# Source_Selection.net
KiCad netlist of a schematic drawn in Altium Designer
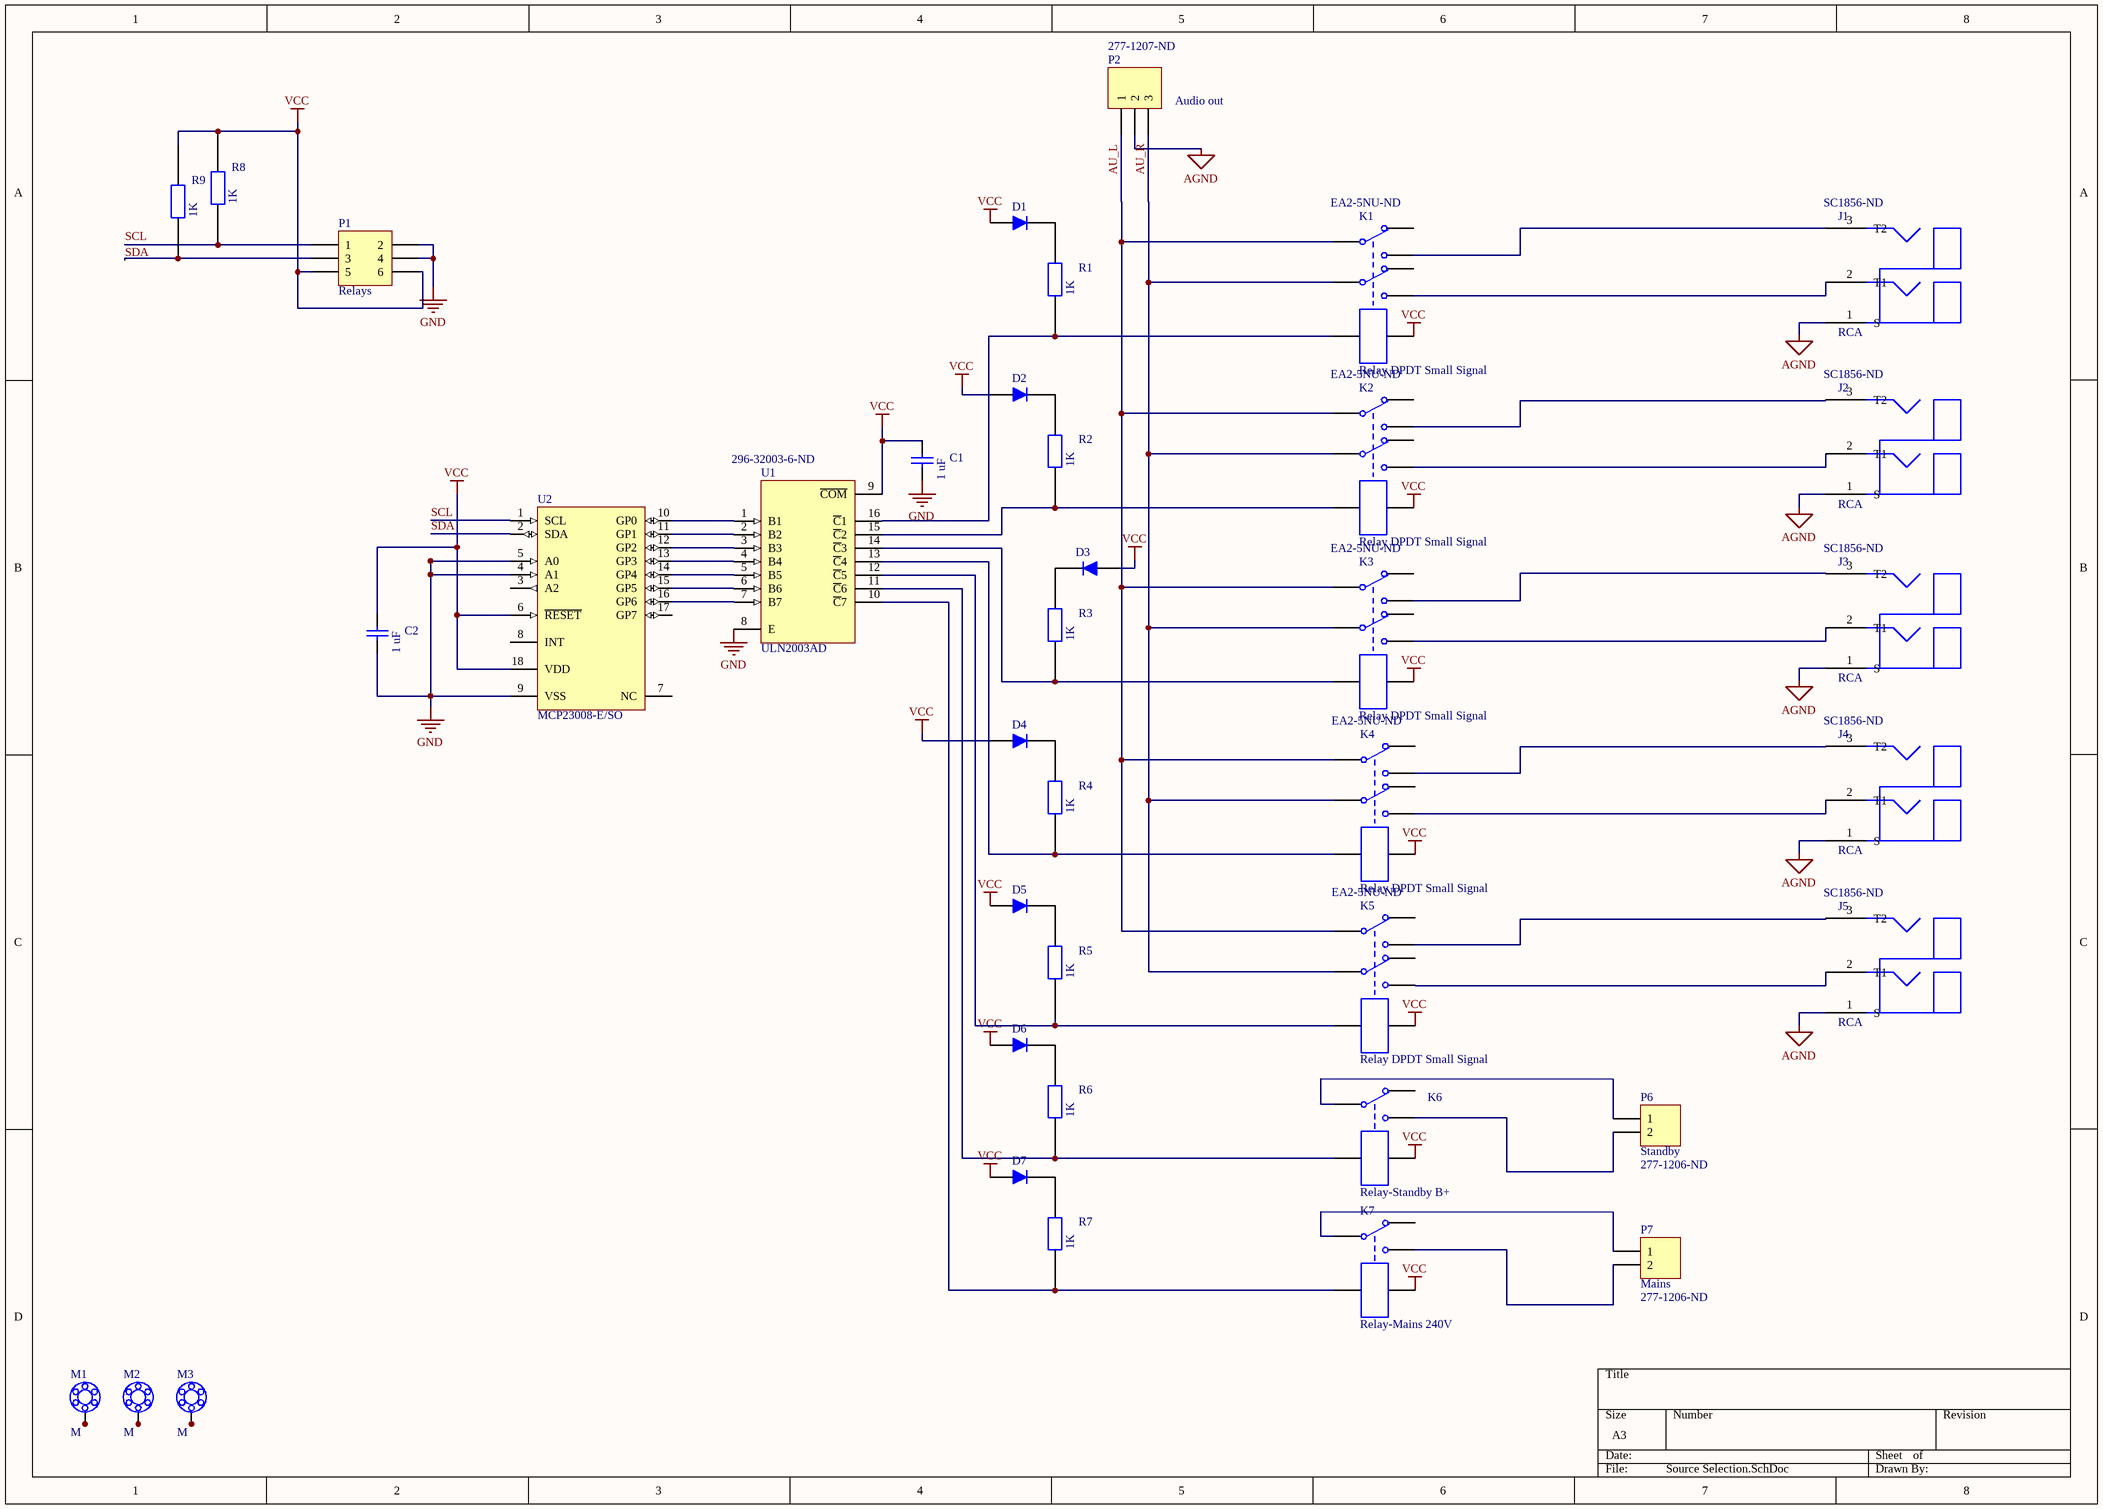
[diagram p0: Source Selection.SchDoc]

(export (version "E")
  (design (tool "Eeschema 10.0.6"))
  (components
    (comp (ref "C1")
      (value "GCM188R71C105KA64D")
      (footprint "CAPC1608")
      (description "Multilayer Ceramic Capacitors MLCC - SMD/SMT 0603 1.0uF 16volts X7R 10%")
      (fields (field (name "MANUFACTURER") "Murata Electronics") (field (name "TOLERANCE") "10 %"))
      (libsource (lib "Schlib1") (part "GCM188R71C105KA64D"))
    )
    (comp (ref "C2")
      (value "GCM188R71C105KA64D")
      (footprint "CAPC1608")
      (description "Multilayer Ceramic Capacitors MLCC - SMD/SMT 0603 1.0uF 16volts X7R 10%")
      (fields (field (name "MANUFACTURER") "Murata Electronics") (field (name "TOLERANCE") "10 %"))
      (libsource (lib "Schlib1") (part "GCM188R71C105KA64D"))
    )
    (comp (ref "D1")
      (value "LTST-C191KGKT")
      (footprint "LEDC1608M_AK")
      (description "LED GREEN CLEAR 0603 SMD")
      (fields (field (name "MANUFACTURER") "Lite-On Inc."))
      (libsource (lib "Schlib1") (part "LTST-C191KGKT"))
    )
    (comp (ref "D2")
      (value "LTST-C191KGKT")
      (footprint "LEDC1608M_AK")
      (description "LED GREEN CLEAR 0603 SMD")
      (fields (field (name "MANUFACTURER") "Lite-On Inc."))
      (libsource (lib "Schlib1") (part "LTST-C191KGKT"))
    )
    (comp (ref "D3")
      (value "LTST-C191KGKT")
      (footprint "LEDC1608M_AK")
      (description "LED GREEN CLEAR 0603 SMD")
      (fields (field (name "MANUFACTURER") "Lite-On Inc."))
      (libsource (lib "Schlib1") (part "LTST-C191KGKT"))
    )
    (comp (ref "D4")
      (value "LTST-C191KGKT")
      (footprint "LEDC1608M_AK")
      (description "LED GREEN CLEAR 0603 SMD")
      (fields (field (name "MANUFACTURER") "Lite-On Inc."))
      (libsource (lib "Schlib1") (part "LTST-C191KGKT"))
    )
    (comp (ref "D5")
      (value "LTST-C191KGKT")
      (footprint "LEDC1608M_AK")
      (description "LED GREEN CLEAR 0603 SMD")
      (fields (field (name "MANUFACTURER") "Lite-On Inc."))
      (libsource (lib "Schlib1") (part "LTST-C191KGKT"))
    )
    (comp (ref "D6")
      (value "LTST-C191KGKT")
      (footprint "LEDC1608M_AK")
      (description "LED GREEN CLEAR 0603 SMD")
      (fields (field (name "MANUFACTURER") "Lite-On Inc."))
      (libsource (lib "Schlib1") (part "LTST-C191KGKT"))
    )
    (comp (ref "D7")
      (value "LTST-C191KGKT")
      (footprint "LEDC1608M_AK")
      (description "LED GREEN CLEAR 0603 SMD")
      (fields (field (name "MANUFACTURER") "Lite-On Inc."))
      (libsource (lib "Schlib1") (part "LTST-C191KGKT"))
    )
    (comp (ref "J1")
      (value "RCA")
      (footprint "PJRAS1X2S01AUX")
      (fields
        (field (name "SUPPLIER PART NUMBER 1") "SC1856-ND")
        (field (name "MANUFACTURER") "Switchcraft Inc.")
        (field (name "MANUFACTURER PART NUMBER") "PJRAS1X2S01AUX")
      )
      (libsource (lib "Relay Board") (part "RCA Dual PCB"))
    )
    (comp (ref "J2")
      (value "RCA")
      (footprint "PJRAS1X2S01AUX")
      (fields
        (field (name "SUPPLIER PART NUMBER 1") "SC1856-ND")
        (field (name "MANUFACTURER") "Switchcraft Inc.")
        (field (name "MANUFACTURER PART NUMBER") "PJRAS1X2S01AUX")
      )
      (libsource (lib "Relay Board") (part "RCA Dual PCB"))
    )
    (comp (ref "J3")
      (value "RCA")
      (footprint "PJRAS1X2S01AUX")
      (fields
        (field (name "SUPPLIER PART NUMBER 1") "SC1856-ND")
        (field (name "MANUFACTURER") "Switchcraft Inc.")
        (field (name "MANUFACTURER PART NUMBER") "PJRAS1X2S01AUX")
      )
      (libsource (lib "Relay Board") (part "RCA Dual PCB"))
    )
    (comp (ref "J4")
      (value "RCA")
      (footprint "PJRAS1X2S01AUX")
      (fields
        (field (name "SUPPLIER PART NUMBER 1") "SC1856-ND")
        (field (name "MANUFACTURER") "Switchcraft Inc.")
        (field (name "MANUFACTURER PART NUMBER") "PJRAS1X2S01AUX")
      )
      (libsource (lib "Relay Board") (part "RCA Dual PCB"))
    )
    (comp (ref "J5")
      (value "RCA")
      (footprint "PJRAS1X2S01AUX")
      (fields
        (field (name "SUPPLIER PART NUMBER 1") "SC1856-ND")
        (field (name "MANUFACTURER") "Switchcraft Inc.")
        (field (name "MANUFACTURER PART NUMBER") "PJRAS1X2S01AUX")
      )
      (libsource (lib "Relay Board") (part "RCA Dual PCB"))
    )
    (comp (ref "K1")
      (value "Relay DPDT Small Signal")
      (footprint "DIP-P10")
      (fields
        (field (name "SUPPLIER PART NUMBER 1") "EA2-5NU-ND")
        (field (name "MANUFACTURER") "Kemet")
        (field (name "MANUFACTURER PART NUMBER") "EA2-5NU")
      )
      (libsource (lib "Relay Board") (part "Relay DPDT Small Signal"))
    )
    (comp (ref "K2")
      (value "Relay DPDT Small Signal")
      (footprint "DIP-P10")
      (fields
        (field (name "SUPPLIER PART NUMBER 1") "EA2-5NU-ND")
        (field (name "MANUFACTURER") "Kemet")
        (field (name "MANUFACTURER PART NUMBER") "EA2-5NU")
      )
      (libsource (lib "Relay Board") (part "Relay DPDT Small Signal"))
    )
    (comp (ref "K3")
      (value "Relay DPDT Small Signal")
      (footprint "DIP-P10")
      (fields
        (field (name "SUPPLIER PART NUMBER 1") "EA2-5NU-ND")
        (field (name "MANUFACTURER") "Kemet")
        (field (name "MANUFACTURER PART NUMBER") "EA2-5NU")
      )
      (libsource (lib "Relay Board") (part "Relay DPDT Small Signal"))
    )
    (comp (ref "K4")
      (value "Relay DPDT Small Signal")
      (footprint "DIP-P10")
      (fields
        (field (name "SUPPLIER PART NUMBER 1") "EA2-5NU-ND")
        (field (name "MANUFACTURER") "Kemet")
        (field (name "MANUFACTURER PART NUMBER") "EA2-5NU")
      )
      (libsource (lib "Relay Board") (part "Relay DPDT Small Signal"))
    )
    (comp (ref "K5")
      (value "Relay DPDT Small Signal")
      (footprint "DIP-P10")
      (fields
        (field (name "SUPPLIER PART NUMBER 1") "EA2-5NU-ND")
        (field (name "MANUFACTURER") "Kemet")
        (field (name "MANUFACTURER PART NUMBER") "EA2-5NU")
      )
      (libsource (lib "Relay Board") (part "Relay DPDT Small Signal"))
    )
    (comp (ref "K6")
      (value "Relay-Standby B+")
      (footprint "RELAY_SPDT")
      (libsource (lib "Relay Board") (part "Relay SPDT"))
    )
    (comp (ref "K7")
      (value "Relay-Mains 240V")
      (footprint "RELAY_SPDT")
      (libsource (lib "Relay Board") (part "Relay SPDT"))
    )
    (comp (ref "M1")
      (value "M")
      (footprint "MOUNTING")
      (description "MOUNTING HOLE - NON INSTALLABLE")
      (libsource (lib "vh_altium_library") (part "MOUNTING"))
    )
    (comp (ref "M2")
      (value "M")
      (footprint "MOUNTING")
      (description "MOUNTING HOLE - NON INSTALLABLE")
      (libsource (lib "vh_altium_library") (part "MOUNTING"))
    )
    (comp (ref "M3")
      (value "M")
      (footprint "MOUNTING")
      (description "MOUNTING HOLE - NON INSTALLABLE")
      (libsource (lib "vh_altium_library") (part "MOUNTING"))
    )
    (comp (ref "P1")
      (value "Relays")
      (footprint "Control_ver2_rev1_dale:IDC2.54-H6C")
      (description "Header, 3-Pin, Dual row, Right Angle")
      (fields
        (field (name "MANUFACTURER") "Wurth Electronics Inc")
        (field (name "MANUFACTURER PART NUMBER") "61200621721")
        (field (name "PUBLISHER") "Altium Limited")
      )
      (libsource (lib "Miscellaneous Connectors") (part "Header 3X2H"))
    )
    (comp (ref "P2")
      (value "Audio out")
      (footprint "PH_TERM_3")
      (description "Header, 3-Pin")
      (fields
        (field (name "SUPPLIER PART NUMBER 1") "277-1207-ND")
        (field (name "MANUFACTURER") "Phoenix Contact")
        (field (name "MANUFACTURER PART NUMBER") "1803280")
        (field (name "PUBLISHER") "Altium Limited")
      )
      (libsource (lib "Miscellaneous Connectors") (part "Header 3"))
    )
    (comp (ref "P6")
      (value "Standby")
      (footprint "PH_TERM_2")
      (description "Header, 2-Pin")
      (fields
        (field (name "SUPPLIER PART NUMBER 1") "277-1206-ND")
        (field (name "MANUFACTURER") "Phoenix Contact")
        (field (name "MANUFACTURER PART NUMBER") "1803277")
        (field (name "PUBLISHER") "Altium Limited")
      )
      (libsource (lib "Miscellaneous Connectors") (part "Header 2"))
    )
    (comp (ref "P7")
      (value "Mains")
      (footprint "PH_TERM_2")
      (description "Header, 2-Pin")
      (fields
        (field (name "SUPPLIER PART NUMBER 1") "277-1206-ND")
        (field (name "MANUFACTURER") "Phoenix Contact")
        (field (name "MANUFACTURER PART NUMBER") "1803277")
        (field (name "PUBLISHER") "Altium Limited")
      )
      (libsource (lib "Miscellaneous Connectors") (part "Header 2"))
    )
    (comp (ref "R1")
      (value "CR0603-FX-1001ELF")
      (footprint "RESC1608")
      (description "RES SMD 1K OHM 1% 1/10W 0603")
      (fields (field (name "MANUFACTURER") "Bourns Inc.") (field (name "TOLERANCE") "±1%"))
      (libsource (lib "Schlib1") (part "CR0603-FX-1001ELF"))
    )
    (comp (ref "R2")
      (value "CR0603-FX-1001ELF")
      (footprint "RESC1608")
      (description "RES SMD 1K OHM 1% 1/10W 0603")
      (fields (field (name "MANUFACTURER") "Bourns Inc.") (field (name "TOLERANCE") "±1%"))
      (libsource (lib "Schlib1") (part "CR0603-FX-1001ELF"))
    )
    (comp (ref "R3")
      (value "CR0603-FX-1001ELF")
      (footprint "RESC1608")
      (description "RES SMD 1K OHM 1% 1/10W 0603")
      (fields (field (name "MANUFACTURER") "Bourns Inc.") (field (name "TOLERANCE") "±1%"))
      (libsource (lib "Schlib1") (part "CR0603-FX-1001ELF"))
    )
    (comp (ref "R4")
      (value "CR0603-FX-1001ELF")
      (footprint "RESC1608")
      (description "RES SMD 1K OHM 1% 1/10W 0603")
      (fields (field (name "MANUFACTURER") "Bourns Inc.") (field (name "TOLERANCE") "±1%"))
      (libsource (lib "Schlib1") (part "CR0603-FX-1001ELF"))
    )
    (comp (ref "R5")
      (value "CR0603-FX-1001ELF")
      (footprint "RESC1608")
      (description "RES SMD 1K OHM 1% 1/10W 0603")
      (fields (field (name "MANUFACTURER") "Bourns Inc.") (field (name "TOLERANCE") "±1%"))
      (libsource (lib "Schlib1") (part "CR0603-FX-1001ELF"))
    )
    (comp (ref "R6")
      (value "CR0603-FX-1001ELF")
      (footprint "RESC1608")
      (description "RES SMD 1K OHM 1% 1/10W 0603")
      (fields (field (name "MANUFACTURER") "Bourns Inc.") (field (name "TOLERANCE") "±1%"))
      (libsource (lib "Schlib1") (part "CR0603-FX-1001ELF"))
    )
    (comp (ref "R7")
      (value "CR0603-FX-1001ELF")
      (footprint "RESC1608")
      (description "RES SMD 1K OHM 1% 1/10W 0603")
      (fields (field (name "MANUFACTURER") "Bourns Inc.") (field (name "TOLERANCE") "±1%"))
      (libsource (lib "Schlib1") (part "CR0603-FX-1001ELF"))
    )
    (comp (ref "R8")
      (value "CR0603-FX-1001ELF")
      (footprint "RESC1608")
      (description "RES SMD 1K OHM 1% 1/10W 0603")
      (fields (field (name "MANUFACTURER") "Bourns Inc.") (field (name "TOLERANCE") "±1%"))
      (libsource (lib "Schlib1") (part "CR0603-FX-1001ELF"))
    )
    (comp (ref "R9")
      (value "CR0603-FX-1001ELF")
      (footprint "RESC1608")
      (description "RES SMD 1K OHM 1% 1/10W 0603")
      (fields (field (name "MANUFACTURER") "Bourns Inc.") (field (name "TOLERANCE") "±1%"))
      (libsource (lib "Schlib1") (part "CR0603-FX-1001ELF"))
    )
    (comp (ref "U1")
      (value "ULN2003AD")
      (footprint "D016_N")
      (description "Darlington Transistor Array")
      (fields
        (field (name "SUPPLIER PART NUMBER 1") "296-32003-6-ND")
        (field (name "MANUFACTURER") "Texas Instruments")
        (field (name "MANUFACTURER PART NUMBER") "ULN2003ADRG4")
        (field (name "PUBLISHER") "Altium Limited")
      )
      (libsource (lib "TI Interface Darlington Driver") (part "ULN2003AD"))
    )
    (comp (ref "U2")
      (value "MCP23008-E/SO")
      (footprint "SOIC-SO18_N")
      (description "8-Bit I/O Expander with Serial Interface, 18-Pin SOIC, Extended Temperature")
      (fields
        (field (name "MANUFACTURER") "Microchip Technology")
        (field (name "PUBLISHER") "Altium Limited")
      )
      (libsource (lib "Microchip Interface") (part "MCP23008-E/SO"))
    )
  )
  (nets
    (net (code "1") (name "/AU_L") (class "Default")
      (node (ref "K1") (pin "3") (pinfunction "3_3") (pintype "passive"))
      (node (ref "K2") (pin "3") (pinfunction "3_3") (pintype "passive"))
      (node (ref "K3") (pin "3") (pinfunction "3_3") (pintype "passive"))
      (node (ref "K4") (pin "3") (pinfunction "3_3") (pintype "passive"))
      (node (ref "K5") (pin "3") (pinfunction "3_3") (pintype "passive"))
      (node (ref "P2") (pin "1") (pinfunction "1_1") (pintype "passive"))
    )
    (net (code "2") (name "/AU_R") (class "Default")
      (node (ref "K1") (pin "8") (pinfunction "8_8") (pintype "passive"))
      (node (ref "K2") (pin "8") (pinfunction "8_8") (pintype "passive"))
      (node (ref "K3") (pin "8") (pinfunction "8_8") (pintype "passive"))
      (node (ref "K4") (pin "8") (pinfunction "8_8") (pintype "passive"))
      (node (ref "K5") (pin "8") (pinfunction "8_8") (pintype "passive"))
      (node (ref "P2") (pin "3") (pinfunction "3_3") (pintype "passive"))
    )
    (net (code "3") (name "/SCL") (class "Default")
      (node (ref "P1") (pin "1") (pinfunction "1_1") (pintype "passive"))
      (node (ref "R8") (pin "1") (pintype "passive"))
      (node (ref "U2") (pin "1") (pinfunction "SCL_1") (pintype "input"))
    )
    (net (code "4") (name "/SDA") (class "Default")
      (node (ref "P1") (pin "3") (pinfunction "3_3") (pintype "passive"))
      (node (ref "R9") (pin "1") (pintype "passive"))
      (node (ref "U2") (pin "2") (pinfunction "SDA_2") (pintype "bidirectional"))
    )
    (net (code "5") (name "AGND") (class "Default")
      (node (ref "J1") (pin "1") (pinfunction "S_1") (pintype "power_in"))
      (node (ref "J2") (pin "1") (pinfunction "S_1") (pintype "power_in"))
      (node (ref "J3") (pin "1") (pinfunction "S_1") (pintype "power_in"))
      (node (ref "J4") (pin "1") (pinfunction "S_1") (pintype "power_in"))
      (node (ref "J5") (pin "1") (pinfunction "S_1") (pintype "power_in"))
      (node (ref "P2") (pin "2") (pinfunction "2_2") (pintype "passive"))
    )
    (net (code "6") (name "GND") (class "Default")
      (node (ref "C1") (pin "1") (pinfunction "1_1") (pintype "passive"))
      (node (ref "C2") (pin "1") (pinfunction "1_1") (pintype "passive"))
      (node (ref "P1") (pin "2") (pinfunction "2_2") (pintype "passive"))
      (node (ref "P1") (pin "4") (pinfunction "4_4") (pintype "passive"))
      (node (ref "U1") (pin "8") (pinfunction "E_8") (pintype "power_in"))
      (node (ref "U2") (pin "4") (pinfunction "A1_4") (pintype "input"))
      (node (ref "U2") (pin "5") (pinfunction "A0_5") (pintype "input"))
      (node (ref "U2") (pin "9") (pinfunction "VSS_9") (pintype "power_in"))
    )
    (net (code "7") (name "Net-(D1-PadK)") (class "Default")
      (node (ref "D1") (pin "K") (pinfunction "K_K") (pintype "passive"))
      (node (ref "R1") (pin "2") (pintype "passive"))
    )
    (net (code "8") (name "Net-(D2-PadK)") (class "Default")
      (node (ref "D2") (pin "K") (pinfunction "K_K") (pintype "passive"))
      (node (ref "R2") (pin "2") (pintype "passive"))
    )
    (net (code "9") (name "Net-(D3-PadK)") (class "Default")
      (node (ref "D3") (pin "K") (pinfunction "K_K") (pintype "passive"))
      (node (ref "R3") (pin "2") (pintype "passive"))
    )
    (net (code "10") (name "Net-(D4-PadK)") (class "Default")
      (node (ref "D4") (pin "K") (pinfunction "K_K") (pintype "passive"))
      (node (ref "R4") (pin "2") (pintype "passive"))
    )
    (net (code "11") (name "Net-(D5-PadK)") (class "Default")
      (node (ref "D5") (pin "K") (pinfunction "K_K") (pintype "passive"))
      (node (ref "R5") (pin "2") (pintype "passive"))
    )
    (net (code "12") (name "Net-(D6-PadK)") (class "Default")
      (node (ref "D6") (pin "K") (pinfunction "K_K") (pintype "passive"))
      (node (ref "R6") (pin "2") (pintype "passive"))
    )
    (net (code "13") (name "Net-(D7-PadK)") (class "Default")
      (node (ref "D7") (pin "K") (pinfunction "K_K") (pintype "passive"))
      (node (ref "R7") (pin "2") (pintype "passive"))
    )
    (net (code "14") (name "Net-(J1-T1)") (class "Default")
      (node (ref "J1") (pin "2") (pinfunction "T1_2") (pintype "power_in"))
      (node (ref "K1") (pin "7") (pinfunction "7_7") (pintype "passive"))
    )
    (net (code "15") (name "Net-(J1-T2)") (class "Default")
      (node (ref "J1") (pin "3") (pinfunction "T2_3") (pintype "power_in"))
      (node (ref "K1") (pin "4") (pinfunction "4_4") (pintype "passive"))
    )
    (net (code "16") (name "Net-(J2-T1)") (class "Default")
      (node (ref "J2") (pin "2") (pinfunction "T1_2") (pintype "power_in"))
      (node (ref "K2") (pin "7") (pinfunction "7_7") (pintype "passive"))
    )
    (net (code "17") (name "Net-(J2-T2)") (class "Default")
      (node (ref "J2") (pin "3") (pinfunction "T2_3") (pintype "power_in"))
      (node (ref "K2") (pin "4") (pinfunction "4_4") (pintype "passive"))
    )
    (net (code "18") (name "Net-(J3-T1)") (class "Default")
      (node (ref "J3") (pin "2") (pinfunction "T1_2") (pintype "power_in"))
      (node (ref "K3") (pin "7") (pinfunction "7_7") (pintype "passive"))
    )
    (net (code "19") (name "Net-(J3-T2)") (class "Default")
      (node (ref "J3") (pin "3") (pinfunction "T2_3") (pintype "power_in"))
      (node (ref "K3") (pin "4") (pinfunction "4_4") (pintype "passive"))
    )
    (net (code "20") (name "Net-(J4-T1)") (class "Default")
      (node (ref "J4") (pin "2") (pinfunction "T1_2") (pintype "power_in"))
      (node (ref "K4") (pin "7") (pinfunction "7_7") (pintype "passive"))
    )
    (net (code "21") (name "Net-(J4-T2)") (class "Default")
      (node (ref "J4") (pin "3") (pinfunction "T2_3") (pintype "power_in"))
      (node (ref "K4") (pin "4") (pinfunction "4_4") (pintype "passive"))
    )
    (net (code "22") (name "Net-(J5-T1)") (class "Default")
      (node (ref "J5") (pin "2") (pinfunction "T1_2") (pintype "power_in"))
      (node (ref "K5") (pin "7") (pinfunction "7_7") (pintype "passive"))
    )
    (net (code "23") (name "Net-(J5-T2)") (class "Default")
      (node (ref "J5") (pin "3") (pinfunction "T2_3") (pintype "power_in"))
      (node (ref "K5") (pin "4") (pinfunction "4_4") (pintype "passive"))
    )
    (net (code "24") (name "Net-(K6-Pad2)") (class "Default")
      (node (ref "K6") (pin "2") (pinfunction "2_2") (pintype "passive"))
      (node (ref "P6") (pin "1") (pinfunction "1_1") (pintype "passive"))
    )
    (net (code "25") (name "Net-(K6-Pad5)") (class "Default")
      (node (ref "K6") (pin "5") (pinfunction "5_5") (pintype "passive"))
      (node (ref "P6") (pin "2") (pinfunction "2_2") (pintype "passive"))
    )
    (net (code "26") (name "Net-(K7-Pad2)") (class "Default")
      (node (ref "K7") (pin "2") (pinfunction "2_2") (pintype "passive"))
      (node (ref "P7") (pin "1") (pinfunction "1_1") (pintype "passive"))
    )
    (net (code "27") (name "Net-(K7-Pad5)") (class "Default")
      (node (ref "K7") (pin "5") (pinfunction "5_5") (pintype "passive"))
      (node (ref "P7") (pin "2") (pinfunction "2_2") (pintype "passive"))
    )
    (net (code "28") (name "Net-(M1-Pad1)") (class "Default")
      (node (ref "M1") (pin "1") (pinfunction "1_1") (pintype "passive"))
      (node (ref "M1") (pin "2") (pinfunction "2_2") (pintype "passive"))
      (node (ref "M1") (pin "3") (pinfunction "3_3") (pintype "passive"))
      (node (ref "M1") (pin "4") (pinfunction "4_4") (pintype "passive"))
      (node (ref "M1") (pin "5") (pinfunction "5_5") (pintype "passive"))
      (node (ref "M1") (pin "6") (pinfunction "6_6") (pintype "passive"))
      (node (ref "M1") (pin "7") (pinfunction "7_7") (pintype "passive"))
    )
    (net (code "29") (name "Net-(M2-Pad1)") (class "Default")
      (node (ref "M2") (pin "1") (pinfunction "1_1") (pintype "passive"))
      (node (ref "M2") (pin "2") (pinfunction "2_2") (pintype "passive"))
      (node (ref "M2") (pin "3") (pinfunction "3_3") (pintype "passive"))
      (node (ref "M2") (pin "4") (pinfunction "4_4") (pintype "passive"))
      (node (ref "M2") (pin "5") (pinfunction "5_5") (pintype "passive"))
      (node (ref "M2") (pin "6") (pinfunction "6_6") (pintype "passive"))
      (node (ref "M2") (pin "7") (pinfunction "7_7") (pintype "passive"))
    )
    (net (code "30") (name "Net-(M3-Pad1)") (class "Default")
      (node (ref "M3") (pin "1") (pinfunction "1_1") (pintype "passive"))
      (node (ref "M3") (pin "2") (pinfunction "2_2") (pintype "passive"))
      (node (ref "M3") (pin "3") (pinfunction "3_3") (pintype "passive"))
      (node (ref "M3") (pin "4") (pinfunction "4_4") (pintype "passive"))
      (node (ref "M3") (pin "5") (pinfunction "5_5") (pintype "passive"))
      (node (ref "M3") (pin "6") (pinfunction "6_6") (pintype "passive"))
      (node (ref "M3") (pin "7") (pinfunction "7_7") (pintype "passive"))
    )
    (net (code "31") (name "Net-(U1-B1)") (class "Default")
      (node (ref "U1") (pin "1") (pinfunction "B1_1") (pintype "input"))
      (node (ref "U2") (pin "10") (pinfunction "GP0_10") (pintype "bidirectional"))
    )
    (net (code "32") (name "Net-(U1-B2)") (class "Default")
      (node (ref "U1") (pin "2") (pinfunction "B2_2") (pintype "input"))
      (node (ref "U2") (pin "11") (pinfunction "GP1_11") (pintype "bidirectional"))
    )
    (net (code "33") (name "Net-(U1-B3)") (class "Default")
      (node (ref "U1") (pin "3") (pinfunction "B3_3") (pintype "input"))
      (node (ref "U2") (pin "12") (pinfunction "GP2_12") (pintype "bidirectional"))
    )
    (net (code "34") (name "Net-(U1-B4)") (class "Default")
      (node (ref "U1") (pin "4") (pinfunction "B4_4") (pintype "input"))
      (node (ref "U2") (pin "13") (pinfunction "GP3_13") (pintype "bidirectional"))
    )
    (net (code "35") (name "Net-(U1-B5)") (class "Default")
      (node (ref "U1") (pin "5") (pinfunction "B5_5") (pintype "input"))
      (node (ref "U2") (pin "14") (pinfunction "GP4_14") (pintype "bidirectional"))
    )
    (net (code "36") (name "Net-(U1-B6)") (class "Default")
      (node (ref "U1") (pin "6") (pinfunction "B6_6") (pintype "input"))
      (node (ref "U2") (pin "15") (pinfunction "GP5_15") (pintype "bidirectional"))
    )
    (net (code "37") (name "Net-(U1-B7)") (class "Default")
      (node (ref "U1") (pin "7") (pinfunction "B7_7") (pintype "input"))
      (node (ref "U2") (pin "16") (pinfunction "GP6_16") (pintype "bidirectional"))
    )
    (net (code "38") (name "Net-(U1-~{C}1)") (class "Default")
      (node (ref "K1") (pin "1") (pinfunction "1_1") (pintype "passive"))
      (node (ref "R1") (pin "1") (pintype "passive"))
      (node (ref "U1") (pin "16") (pinfunction "~{C}1_16") (pintype "open_collector"))
    )
    (net (code "39") (name "Net-(U1-~{C}2)") (class "Default")
      (node (ref "K2") (pin "1") (pinfunction "1_1") (pintype "passive"))
      (node (ref "R2") (pin "1") (pintype "passive"))
      (node (ref "U1") (pin "15") (pinfunction "~{C}2_15") (pintype "open_collector"))
    )
    (net (code "40") (name "Net-(U1-~{C}3)") (class "Default")
      (node (ref "K3") (pin "1") (pinfunction "1_1") (pintype "passive"))
      (node (ref "R3") (pin "1") (pintype "passive"))
      (node (ref "U1") (pin "14") (pinfunction "~{C}3_14") (pintype "open_collector"))
    )
    (net (code "41") (name "Net-(U1-~{C}4)") (class "Default")
      (node (ref "K4") (pin "1") (pinfunction "1_1") (pintype "passive"))
      (node (ref "R4") (pin "1") (pintype "passive"))
      (node (ref "U1") (pin "13") (pinfunction "~{C}4_13") (pintype "open_collector"))
    )
    (net (code "42") (name "Net-(U1-~{C}5)") (class "Default")
      (node (ref "K5") (pin "1") (pinfunction "1_1") (pintype "passive"))
      (node (ref "R5") (pin "1") (pintype "passive"))
      (node (ref "U1") (pin "12") (pinfunction "~{C}5_12") (pintype "open_collector"))
    )
    (net (code "43") (name "Net-(U1-~{C}6)") (class "Default")
      (node (ref "K6") (pin "1") (pinfunction "1_1") (pintype "passive"))
      (node (ref "R6") (pin "1") (pintype "passive"))
      (node (ref "U1") (pin "11") (pinfunction "~{C}6_11") (pintype "open_collector"))
    )
    (net (code "44") (name "Net-(U1-~{C}7)") (class "Default")
      (node (ref "K7") (pin "1") (pinfunction "1_1") (pintype "passive"))
      (node (ref "R7") (pin "1") (pintype "passive"))
      (node (ref "U1") (pin "10") (pinfunction "~{C}7_10") (pintype "open_collector"))
    )
    (net (code "45") (name "VCC") (class "Default")
      (node (ref "C1") (pin "2") (pinfunction "2_2") (pintype "passive"))
      (node (ref "C2") (pin "2") (pinfunction "2_2") (pintype "passive"))
      (node (ref "D1") (pin "A") (pinfunction "A_A") (pintype "passive"))
      (node (ref "D2") (pin "A") (pinfunction "A_A") (pintype "passive"))
      (node (ref "D3") (pin "A") (pinfunction "A_A") (pintype "passive"))
      (node (ref "D4") (pin "A") (pinfunction "A_A") (pintype "passive"))
      (node (ref "D5") (pin "A") (pinfunction "A_A") (pintype "passive"))
      (node (ref "D6") (pin "A") (pinfunction "A_A") (pintype "passive"))
      (node (ref "D7") (pin "A") (pinfunction "A_A") (pintype "passive"))
      (node (ref "K1") (pin "10") (pinfunction "10_10") (pintype "passive"))
      (node (ref "K2") (pin "10") (pinfunction "10_10") (pintype "passive"))
      (node (ref "K3") (pin "10") (pinfunction "10_10") (pintype "passive"))
      (node (ref "K4") (pin "10") (pinfunction "10_10") (pintype "passive"))
      (node (ref "K5") (pin "10") (pinfunction "10_10") (pintype "passive"))
      (node (ref "K6") (pin "3") (pinfunction "3_3") (pintype "passive"))
      (node (ref "K7") (pin "3") (pinfunction "3_3") (pintype "passive"))
      (node (ref "P1") (pin "5") (pinfunction "5_5") (pintype "passive"))
      (node (ref "P1") (pin "6") (pinfunction "6_6") (pintype "passive"))
      (node (ref "R8") (pin "2") (pintype "passive"))
      (node (ref "R9") (pin "2") (pintype "passive"))
      (node (ref "U1") (pin "9") (pinfunction "~{COM}_9") (pintype "passive"))
      (node (ref "U2") (pin "18") (pinfunction "VDD_18") (pintype "power_in"))
      (node (ref "U2") (pin "6") (pinfunction "~{RESET}_6") (pintype "input"))
    )
    (net (code "46") (name "unconnected-(K1-Pad2)") (class "Default")
      (node (ref "K1") (pin "2") (pinfunction "2_2") (pintype "passive"))
    )
    (net (code "47") (name "unconnected-(K1-Pad9)") (class "Default")
      (node (ref "K1") (pin "9") (pinfunction "9_9") (pintype "passive"))
    )
    (net (code "48") (name "unconnected-(K2-Pad2)") (class "Default")
      (node (ref "K2") (pin "2") (pinfunction "2_2") (pintype "passive"))
    )
    (net (code "49") (name "unconnected-(K2-Pad9)") (class "Default")
      (node (ref "K2") (pin "9") (pinfunction "9_9") (pintype "passive"))
    )
    (net (code "50") (name "unconnected-(K3-Pad2)") (class "Default")
      (node (ref "K3") (pin "2") (pinfunction "2_2") (pintype "passive"))
    )
    (net (code "51") (name "unconnected-(K3-Pad9)") (class "Default")
      (node (ref "K3") (pin "9") (pinfunction "9_9") (pintype "passive"))
    )
    (net (code "52") (name "unconnected-(K4-Pad2)") (class "Default")
      (node (ref "K4") (pin "2") (pinfunction "2_2") (pintype "passive"))
    )
    (net (code "53") (name "unconnected-(K4-Pad9)") (class "Default")
      (node (ref "K4") (pin "9") (pinfunction "9_9") (pintype "passive"))
    )
    (net (code "54") (name "unconnected-(K5-Pad2)") (class "Default")
      (node (ref "K5") (pin "2") (pinfunction "2_2") (pintype "passive"))
    )
    (net (code "55") (name "unconnected-(K5-Pad9)") (class "Default")
      (node (ref "K5") (pin "9") (pinfunction "9_9") (pintype "passive"))
    )
    (net (code "56") (name "unconnected-(K6-Pad4)") (class "Default")
      (node (ref "K6") (pin "4") (pinfunction "4_4") (pintype "passive"))
    )
    (net (code "57") (name "unconnected-(K7-Pad4)") (class "Default")
      (node (ref "K7") (pin "4") (pinfunction "4_4") (pintype "passive"))
    )
    (net (code "58") (name "unconnected-(U2-A2-Pad3)") (class "Default")
      (node (ref "U2") (pin "3") (pinfunction "A2_3") (pintype "output"))
    )
    (net (code "59") (name "unconnected-(U2-GP7-Pad17)") (class "Default")
      (node (ref "U2") (pin "17") (pinfunction "GP7_17") (pintype "bidirectional"))
    )
    (net (code "60") (name "unconnected-(U2-INT-Pad8)") (class "Default")
      (node (ref "U2") (pin "8") (pinfunction "INT_8") (pintype "open_collector"))
    )
    (net (code "61") (name "unconnected-(U2-NC-Pad7)") (class "Default")
      (node (ref "U2") (pin "7") (pinfunction "NC_7") (pintype "passive"))
    )
  )
)
